# board.net
KiCad netlist of a schematic drawn in EAGLE
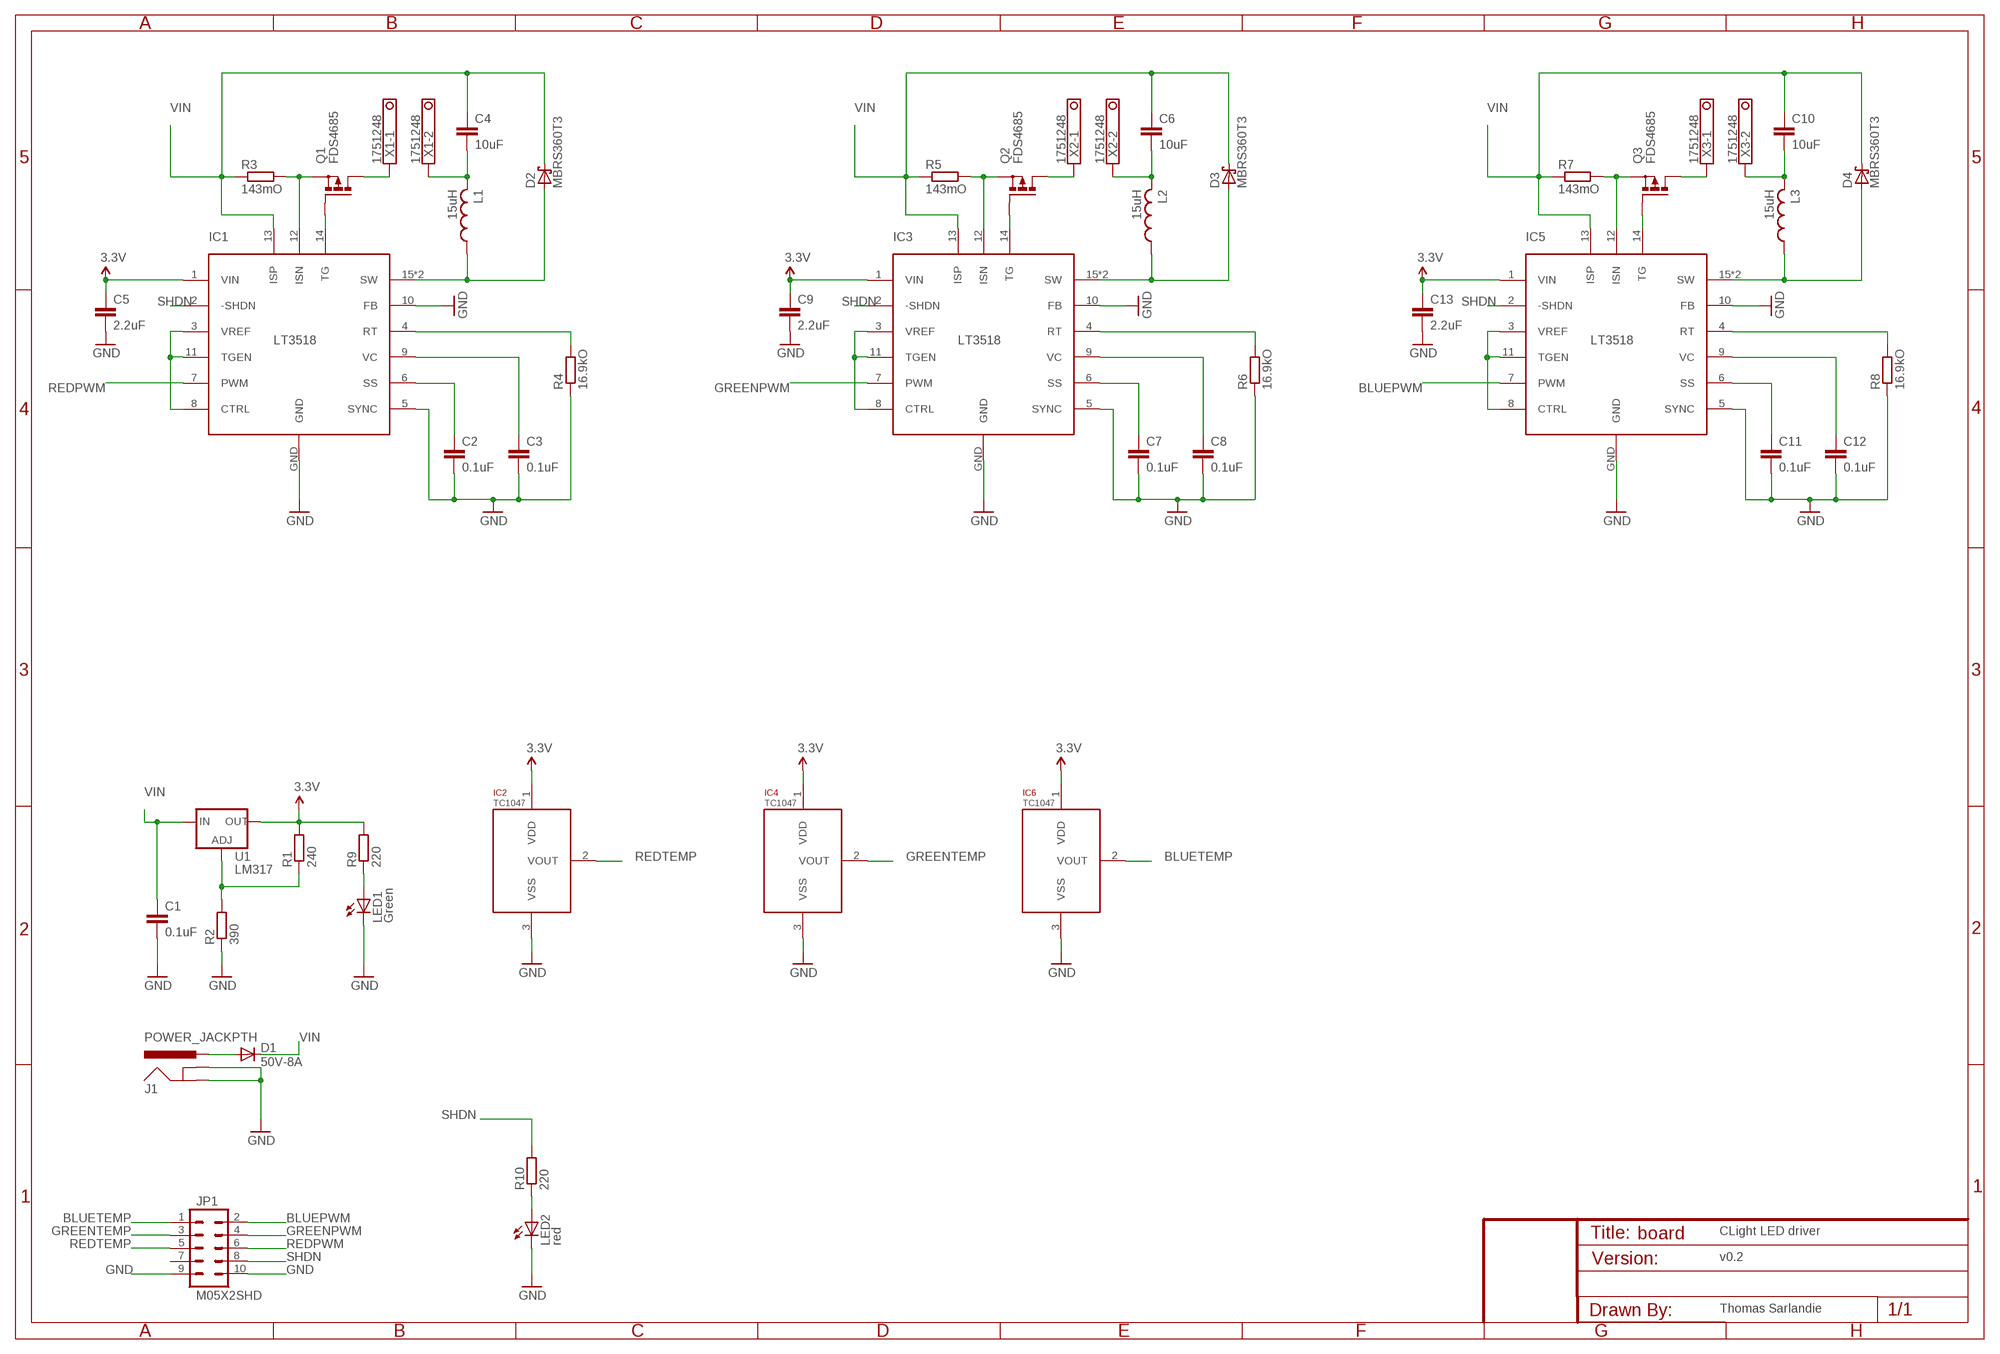
[diagram p0: schematic, sheet 1]

(export (version "E")
  (design (tool "Eeschema 10.0.6"))
  (components
    (comp (ref "C1")
      (value "0.1uF")
      (footprint "eagle-import:C1206")
      (libsource (lib "eagle-import") (part "C-EUC1206"))
    )
    (comp (ref "C2")
      (value "0.1uF")
      (footprint "eagle-import:C1206")
      (libsource (lib "eagle-import") (part "C-EUC1206"))
    )
    (comp (ref "C3")
      (value "0.1uF")
      (footprint "eagle-import:C1206")
      (libsource (lib "eagle-import") (part "C-EUC1206"))
    )
    (comp (ref "C4")
      (value "10uF")
      (footprint "eagle-import:C1206")
      (libsource (lib "eagle-import") (part "C-EUC1206"))
    )
    (comp (ref "C5")
      (value "2.2uF")
      (footprint "eagle-import:C1206")
      (libsource (lib "eagle-import") (part "C-EUC1206"))
    )
    (comp (ref "C6")
      (value "10uF")
      (footprint "eagle-import:C1206")
      (libsource (lib "eagle-import") (part "C-EUC1206"))
    )
    (comp (ref "C7")
      (value "0.1uF")
      (footprint "eagle-import:C1206")
      (libsource (lib "eagle-import") (part "C-EUC1206"))
    )
    (comp (ref "C8")
      (value "0.1uF")
      (footprint "eagle-import:C1206")
      (libsource (lib "eagle-import") (part "C-EUC1206"))
    )
    (comp (ref "C9")
      (value "2.2uF")
      (footprint "eagle-import:C1206")
      (libsource (lib "eagle-import") (part "C-EUC1206"))
    )
    (comp (ref "C10")
      (value "10uF")
      (footprint "eagle-import:C1206")
      (libsource (lib "eagle-import") (part "C-EUC1206"))
    )
    (comp (ref "C11")
      (value "0.1uF")
      (footprint "eagle-import:C1206")
      (libsource (lib "eagle-import") (part "C-EUC1206"))
    )
    (comp (ref "C12")
      (value "0.1uF")
      (footprint "eagle-import:C1206")
      (libsource (lib "eagle-import") (part "C-EUC1206"))
    )
    (comp (ref "C13")
      (value "2.2uF")
      (footprint "eagle-import:C1206")
      (libsource (lib "eagle-import") (part "C-EUC1206"))
    )
    (comp (ref "D1")
      (value "50V-8A")
      (footprint "eagle-import:SMC")
      (libsource (lib "eagle-import") (part "DIODE-SMC"))
    )
    (comp (ref "D2")
      (value "MBRS360T3")
      (footprint "eagle-import:SMC")
      (libsource (lib "eagle-import") (part "MBRS30T34"))
    )
    (comp (ref "D3")
      (value "MBRS360T3")
      (footprint "eagle-import:SMC")
      (libsource (lib "eagle-import") (part "MBRS30T34"))
    )
    (comp (ref "D4")
      (value "MBRS360T3")
      (footprint "eagle-import:SMC")
      (libsource (lib "eagle-import") (part "MBRS30T34"))
    )
    (comp (ref "IC1")
      (value "LT3518TSSOP16-EXPOSED-PAD-LARGE")
      (footprint "eagle-import:TSSOP16-EXPOSED_PAD_LARGE")
      (libsource (lib "eagle-import") (part "LT3518TSSOP16-EXPOSED-PAD-LARGE"))
    )
    (comp (ref "IC2")
      (value "TC1047")
      (footprint "eagle-import:SOT-23B")
      (libsource (lib "eagle-import") (part "TC1047SOT-23B"))
    )
    (comp (ref "IC3")
      (value "LT3518TSSOP16-EXPOSED-PAD-LARGE")
      (footprint "eagle-import:TSSOP16-EXPOSED_PAD_LARGE")
      (libsource (lib "eagle-import") (part "LT3518TSSOP16-EXPOSED-PAD-LARGE"))
    )
    (comp (ref "IC4")
      (value "TC1047")
      (footprint "eagle-import:SOT-23B")
      (libsource (lib "eagle-import") (part "TC1047SOT-23B"))
    )
    (comp (ref "IC5")
      (value "LT3518TSSOP16-EXPOSED-PAD-LARGE")
      (footprint "eagle-import:TSSOP16-EXPOSED_PAD_LARGE")
      (libsource (lib "eagle-import") (part "LT3518TSSOP16-EXPOSED-PAD-LARGE"))
    )
    (comp (ref "IC6")
      (value "TC1047")
      (footprint "eagle-import:SOT-23B")
      (libsource (lib "eagle-import") (part "TC1047SOT-23B"))
    )
    (comp (ref "J1")
      (value "POWER_JACKPTH")
      (footprint "eagle-import:POWER_JACK_PTH")
      (libsource (lib "eagle-import") (part "POWER_JACKPTH"))
    )
    (comp (ref "JP1")
      (value "M05X2SHD")
      (footprint "eagle-import:2X5-SHROUDED")
      (libsource (lib "eagle-import") (part "M05X2SHD"))
    )
    (comp (ref "L1")
      (value "15uH")
      (footprint "eagle-import:L2020")
      (libsource (lib "eagle-import") (part "L-USL2020"))
    )
    (comp (ref "L2")
      (value "15uH")
      (footprint "eagle-import:L2020")
      (libsource (lib "eagle-import") (part "L-USL2020"))
    )
    (comp (ref "L3")
      (value "15uH")
      (footprint "eagle-import:L2020")
      (libsource (lib "eagle-import") (part "L-USL2020"))
    )
    (comp (ref "LED1")
      (value "Green")
      (footprint "eagle-import:LED-1206")
      (libsource (lib "eagle-import") (part "LED1206"))
    )
    (comp (ref "LED2")
      (value "red")
      (footprint "eagle-import:LED-1206")
      (libsource (lib "eagle-import") (part "LED1206"))
    )
    (comp (ref "Q1")
      (value "FDS4685")
      (footprint "eagle-import:SO-08")
      (libsource (lib "eagle-import") (part "P-MOSFET-SO8"))
    )
    (comp (ref "Q2")
      (value "FDS4685")
      (footprint "eagle-import:SO-08")
      (libsource (lib "eagle-import") (part "P-MOSFET-SO8"))
    )
    (comp (ref "Q3")
      (value "FDS4685")
      (footprint "eagle-import:SO-08")
      (libsource (lib "eagle-import") (part "P-MOSFET-SO8"))
    )
    (comp (ref "R1")
      (value "240")
      (footprint "eagle-import:R1206")
      (libsource (lib "eagle-import") (part "R-EU_R1206"))
    )
    (comp (ref "R2")
      (value "390")
      (footprint "eagle-import:R1206")
      (libsource (lib "eagle-import") (part "R-EU_R1206"))
    )
    (comp (ref "R3")
      (value "143mO")
      (footprint "eagle-import:R1206")
      (libsource (lib "eagle-import") (part "R-EU_R1206"))
    )
    (comp (ref "R4")
      (value "16.9kO")
      (footprint "eagle-import:R1206")
      (libsource (lib "eagle-import") (part "R-EU_R1206"))
    )
    (comp (ref "R5")
      (value "143mO")
      (footprint "eagle-import:R1206")
      (libsource (lib "eagle-import") (part "R-EU_R1206"))
    )
    (comp (ref "R6")
      (value "16.9kO")
      (footprint "eagle-import:R1206")
      (libsource (lib "eagle-import") (part "R-EU_R1206"))
    )
    (comp (ref "R7")
      (value "143mO")
      (footprint "eagle-import:R1206")
      (libsource (lib "eagle-import") (part "R-EU_R1206"))
    )
    (comp (ref "R8")
      (value "16.9kO")
      (footprint "eagle-import:R1206")
      (libsource (lib "eagle-import") (part "R-EU_R1206"))
    )
    (comp (ref "R9")
      (value "220")
      (footprint "eagle-import:R1206")
      (libsource (lib "eagle-import") (part "R-EU_R1206"))
    )
    (comp (ref "R10")
      (value "220")
      (footprint "eagle-import:R1206")
      (libsource (lib "eagle-import") (part "R-EU_R1206"))
    )
    (comp (ref "U1")
      (value "LM317")
      (footprint "eagle-import:SOT223")
      (libsource (lib "eagle-import") (part "V_REG_317SMD"))
    )
    (comp (ref "X1")
      (value "1751248")
      (footprint "eagle-import:1751248")
      (libsource (lib "eagle-import") (part "1751248"))
    )
    (comp (ref "X2")
      (value "1751248")
      (footprint "eagle-import:1751248")
      (libsource (lib "eagle-import") (part "1751248"))
    )
    (comp (ref "X3")
      (value "1751248")
      (footprint "eagle-import:1751248")
      (libsource (lib "eagle-import") (part "1751248"))
    )
  )
  (nets
    (net (code "1") (name "/BLUEPWM") (class "Default")
      (node (ref "IC5") (pin "7") (pinfunction "PWM_7") (pintype "bidirectional"))
      (node (ref "JP1") (pin "2") (pinfunction "2_2") (pintype "passive"))
    )
    (net (code "2") (name "/BLUETEMP") (class "Default")
      (node (ref "IC6") (pin "2") (pinfunction "VOUT_2") (pintype "bidirectional"))
      (node (ref "JP1") (pin "1") (pinfunction "1_1") (pintype "passive"))
    )
    (net (code "3") (name "/GREENPWM") (class "Default")
      (node (ref "IC3") (pin "7") (pinfunction "PWM_7") (pintype "bidirectional"))
      (node (ref "JP1") (pin "4") (pinfunction "4_4") (pintype "passive"))
    )
    (net (code "4") (name "/GREENTEMP") (class "Default")
      (node (ref "IC4") (pin "2") (pinfunction "VOUT_2") (pintype "bidirectional"))
      (node (ref "JP1") (pin "3") (pinfunction "3_3") (pintype "passive"))
    )
    (net (code "5") (name "/REDPWM") (class "Default")
      (node (ref "IC1") (pin "7") (pinfunction "PWM_7") (pintype "bidirectional"))
      (node (ref "JP1") (pin "6") (pinfunction "6_6") (pintype "passive"))
    )
    (net (code "6") (name "/REDTEMP") (class "Default")
      (node (ref "IC2") (pin "2") (pinfunction "VOUT_2") (pintype "bidirectional"))
      (node (ref "JP1") (pin "5") (pinfunction "5_5") (pintype "passive"))
    )
    (net (code "7") (name "/SHDN") (class "Default")
      (node (ref "IC1") (pin "2") (pinfunction "-SHDN_2") (pintype "bidirectional"))
      (node (ref "IC3") (pin "2") (pinfunction "-SHDN_2") (pintype "bidirectional"))
      (node (ref "IC5") (pin "2") (pinfunction "-SHDN_2") (pintype "bidirectional"))
      (node (ref "JP1") (pin "8") (pinfunction "8_8") (pintype "passive"))
      (node (ref "R10") (pin "2") (pinfunction "2_2") (pintype "passive"))
    )
    (net (code "8") (name "/VIN") (class "Default")
      (node (ref "C1") (pin "1") (pinfunction "1_1") (pintype "passive"))
      (node (ref "C10") (pin "1") (pinfunction "1_1") (pintype "passive"))
      (node (ref "C4") (pin "1") (pinfunction "1_1") (pintype "passive"))
      (node (ref "C6") (pin "1") (pinfunction "1_1") (pintype "passive"))
      (node (ref "D1") (pin "C") (pinfunction "C_C") (pintype "passive"))
      (node (ref "D2") (pin "C") (pinfunction "C_C") (pintype "passive"))
      (node (ref "D3") (pin "C") (pinfunction "C_C") (pintype "passive"))
      (node (ref "D4") (pin "C") (pinfunction "C_C") (pintype "passive"))
      (node (ref "IC1") (pin "13") (pinfunction "ISP_13") (pintype "bidirectional"))
      (node (ref "IC3") (pin "13") (pinfunction "ISP_13") (pintype "bidirectional"))
      (node (ref "IC5") (pin "13") (pinfunction "ISP_13") (pintype "bidirectional"))
      (node (ref "R3") (pin "1") (pinfunction "1_1") (pintype "passive"))
      (node (ref "R5") (pin "1") (pinfunction "1_1") (pintype "passive"))
      (node (ref "R7") (pin "1") (pinfunction "1_1") (pintype "passive"))
      (node (ref "U1") (pin "3") (pinfunction "IN_3") (pintype "input"))
    )
    (net (code "9") (name "3.3V") (class "Default")
      (node (ref "C13") (pin "1") (pinfunction "1_1") (pintype "passive"))
      (node (ref "C5") (pin "1") (pinfunction "1_1") (pintype "passive"))
      (node (ref "C9") (pin "1") (pinfunction "1_1") (pintype "passive"))
      (node (ref "IC1") (pin "1") (pinfunction "VIN_1") (pintype "bidirectional"))
      (node (ref "IC2") (pin "1") (pinfunction "VDD_1") (pintype "bidirectional"))
      (node (ref "IC3") (pin "1") (pinfunction "VIN_1") (pintype "bidirectional"))
      (node (ref "IC4") (pin "1") (pinfunction "VDD_1") (pintype "bidirectional"))
      (node (ref "IC5") (pin "1") (pinfunction "VIN_1") (pintype "bidirectional"))
      (node (ref "IC6") (pin "1") (pinfunction "VDD_1") (pintype "bidirectional"))
      (node (ref "R1") (pin "2") (pinfunction "2_2") (pintype "passive"))
      (node (ref "R9") (pin "2") (pinfunction "2_2") (pintype "passive"))
      (node (ref "U1") (pin "2") (pinfunction "OUT_2") (pintype "output"))
    )
    (net (code "10") (name "GND") (class "Default")
      (node (ref "C1") (pin "2") (pinfunction "2_2") (pintype "passive"))
      (node (ref "C11") (pin "2") (pinfunction "2_2") (pintype "passive"))
      (node (ref "C12") (pin "2") (pinfunction "2_2") (pintype "passive"))
      (node (ref "C13") (pin "2") (pinfunction "2_2") (pintype "passive"))
      (node (ref "C2") (pin "2") (pinfunction "2_2") (pintype "passive"))
      (node (ref "C3") (pin "2") (pinfunction "2_2") (pintype "passive"))
      (node (ref "C5") (pin "2") (pinfunction "2_2") (pintype "passive"))
      (node (ref "C7") (pin "2") (pinfunction "2_2") (pintype "passive"))
      (node (ref "C8") (pin "2") (pinfunction "2_2") (pintype "passive"))
      (node (ref "C9") (pin "2") (pinfunction "2_2") (pintype "passive"))
      (node (ref "IC1") (pin "10") (pinfunction "FB_10") (pintype "bidirectional"))
      (node (ref "IC1") (pin "5") (pinfunction "SYNC_5") (pintype "bidirectional"))
      (node (ref "IC1") (pin "GND") (pinfunction "GND_GND") (pintype "bidirectional"))
      (node (ref "IC2") (pin "3") (pinfunction "VSS_3") (pintype "bidirectional"))
      (node (ref "IC3") (pin "10") (pinfunction "FB_10") (pintype "bidirectional"))
      (node (ref "IC3") (pin "5") (pinfunction "SYNC_5") (pintype "bidirectional"))
      (node (ref "IC3") (pin "GND") (pinfunction "GND_GND") (pintype "bidirectional"))
      (node (ref "IC4") (pin "3") (pinfunction "VSS_3") (pintype "bidirectional"))
      (node (ref "IC5") (pin "10") (pinfunction "FB_10") (pintype "bidirectional"))
      (node (ref "IC5") (pin "5") (pinfunction "SYNC_5") (pintype "bidirectional"))
      (node (ref "IC5") (pin "GND") (pinfunction "GND_GND") (pintype "bidirectional"))
      (node (ref "IC6") (pin "3") (pinfunction "VSS_3") (pintype "bidirectional"))
      (node (ref "J1") (pin "GND") (pinfunction "GND_GND") (pintype "bidirectional"))
      (node (ref "J1") (pin "GNDBREAK") (pinfunction "GNDBREAK_GNDBREAK") (pintype "bidirectional"))
      (node (ref "JP1") (pin "10") (pinfunction "10_10") (pintype "passive"))
      (node (ref "JP1") (pin "9") (pinfunction "9_9") (pintype "passive"))
      (node (ref "LED1") (pin "C") (pinfunction "C_C") (pintype "passive"))
      (node (ref "LED2") (pin "C") (pinfunction "C_C") (pintype "passive"))
      (node (ref "R2") (pin "1") (pinfunction "1_1") (pintype "passive"))
      (node (ref "R4") (pin "1") (pinfunction "1_1") (pintype "passive"))
      (node (ref "R6") (pin "1") (pinfunction "1_1") (pintype "passive"))
      (node (ref "R8") (pin "1") (pinfunction "1_1") (pintype "passive"))
    )
    (net (code "11") (name "Net-(D1-PadA)") (class "Default")
      (node (ref "D1") (pin "A") (pinfunction "A_A") (pintype "passive"))
      (node (ref "J1") (pin "PWR") (pinfunction "PWR_PWR") (pintype "bidirectional"))
    )
    (net (code "12") (name "Net-(IC1-CTRL)") (class "Default")
      (node (ref "IC1") (pin "11") (pinfunction "TGEN_11") (pintype "bidirectional"))
      (node (ref "IC1") (pin "3") (pinfunction "VREF_3") (pintype "bidirectional"))
      (node (ref "IC1") (pin "8") (pinfunction "CTRL_8") (pintype "bidirectional"))
    )
    (net (code "13") (name "Net-(IC1-ISN)") (class "Default")
      (node (ref "IC1") (pin "12") (pinfunction "ISN_12") (pintype "bidirectional"))
      (node (ref "Q1") (pin "1") (pinfunction "S_1") (pintype "passive"))
      (node (ref "Q1") (pin "2") (pinfunction "S_2") (pintype "passive"))
      (node (ref "Q1") (pin "3") (pinfunction "S_3") (pintype "passive"))
      (node (ref "R3") (pin "2") (pinfunction "2_2") (pintype "passive"))
    )
    (net (code "14") (name "Net-(IC1-RT)") (class "Default")
      (node (ref "IC1") (pin "4") (pinfunction "RT_4") (pintype "bidirectional"))
      (node (ref "R4") (pin "2") (pinfunction "2_2") (pintype "passive"))
    )
    (net (code "15") (name "Net-(IC1-SS)") (class "Default")
      (node (ref "C2") (pin "1") (pinfunction "1_1") (pintype "passive"))
      (node (ref "IC1") (pin "6") (pinfunction "SS_6") (pintype "bidirectional"))
    )
    (net (code "16") (name "Net-(IC1-TG)") (class "Default")
      (node (ref "IC1") (pin "14") (pinfunction "TG_14") (pintype "bidirectional"))
      (node (ref "Q1") (pin "4") (pinfunction "G_4") (pintype "passive"))
    )
    (net (code "17") (name "Net-(IC1-VC)") (class "Default")
      (node (ref "C3") (pin "1") (pinfunction "1_1") (pintype "passive"))
      (node (ref "IC1") (pin "9") (pinfunction "VC_9") (pintype "bidirectional"))
    )
    (net (code "18") (name "Net-(IC3-CTRL)") (class "Default")
      (node (ref "IC3") (pin "11") (pinfunction "TGEN_11") (pintype "bidirectional"))
      (node (ref "IC3") (pin "3") (pinfunction "VREF_3") (pintype "bidirectional"))
      (node (ref "IC3") (pin "8") (pinfunction "CTRL_8") (pintype "bidirectional"))
    )
    (net (code "19") (name "Net-(IC3-ISN)") (class "Default")
      (node (ref "IC3") (pin "12") (pinfunction "ISN_12") (pintype "bidirectional"))
      (node (ref "Q2") (pin "1") (pinfunction "S_1") (pintype "passive"))
      (node (ref "Q2") (pin "2") (pinfunction "S_2") (pintype "passive"))
      (node (ref "Q2") (pin "3") (pinfunction "S_3") (pintype "passive"))
      (node (ref "R5") (pin "2") (pinfunction "2_2") (pintype "passive"))
    )
    (net (code "20") (name "Net-(IC3-RT)") (class "Default")
      (node (ref "IC3") (pin "4") (pinfunction "RT_4") (pintype "bidirectional"))
      (node (ref "R6") (pin "2") (pinfunction "2_2") (pintype "passive"))
    )
    (net (code "21") (name "Net-(IC3-SS)") (class "Default")
      (node (ref "C7") (pin "1") (pinfunction "1_1") (pintype "passive"))
      (node (ref "IC3") (pin "6") (pinfunction "SS_6") (pintype "bidirectional"))
    )
    (net (code "22") (name "Net-(IC3-TG)") (class "Default")
      (node (ref "IC3") (pin "14") (pinfunction "TG_14") (pintype "bidirectional"))
      (node (ref "Q2") (pin "4") (pinfunction "G_4") (pintype "passive"))
    )
    (net (code "23") (name "Net-(IC3-VC)") (class "Default")
      (node (ref "C8") (pin "1") (pinfunction "1_1") (pintype "passive"))
      (node (ref "IC3") (pin "9") (pinfunction "VC_9") (pintype "bidirectional"))
    )
    (net (code "24") (name "Net-(IC5-CTRL)") (class "Default")
      (node (ref "IC5") (pin "11") (pinfunction "TGEN_11") (pintype "bidirectional"))
      (node (ref "IC5") (pin "3") (pinfunction "VREF_3") (pintype "bidirectional"))
      (node (ref "IC5") (pin "8") (pinfunction "CTRL_8") (pintype "bidirectional"))
    )
    (net (code "25") (name "Net-(IC5-ISN)") (class "Default")
      (node (ref "IC5") (pin "12") (pinfunction "ISN_12") (pintype "bidirectional"))
      (node (ref "Q3") (pin "1") (pinfunction "S_1") (pintype "passive"))
      (node (ref "Q3") (pin "2") (pinfunction "S_2") (pintype "passive"))
      (node (ref "Q3") (pin "3") (pinfunction "S_3") (pintype "passive"))
      (node (ref "R7") (pin "2") (pinfunction "2_2") (pintype "passive"))
    )
    (net (code "26") (name "Net-(IC5-RT)") (class "Default")
      (node (ref "IC5") (pin "4") (pinfunction "RT_4") (pintype "bidirectional"))
      (node (ref "R8") (pin "2") (pinfunction "2_2") (pintype "passive"))
    )
    (net (code "27") (name "Net-(IC5-SS)") (class "Default")
      (node (ref "C11") (pin "1") (pinfunction "1_1") (pintype "passive"))
      (node (ref "IC5") (pin "6") (pinfunction "SS_6") (pintype "bidirectional"))
    )
    (net (code "28") (name "Net-(IC5-TG)") (class "Default")
      (node (ref "IC5") (pin "14") (pinfunction "TG_14") (pintype "bidirectional"))
      (node (ref "Q3") (pin "4") (pinfunction "G_4") (pintype "passive"))
    )
    (net (code "29") (name "Net-(IC5-VC)") (class "Default")
      (node (ref "C12") (pin "1") (pinfunction "1_1") (pintype "passive"))
      (node (ref "IC5") (pin "9") (pinfunction "VC_9") (pintype "bidirectional"))
    )
    (net (code "30") (name "Net-(L1-1)") (class "Default")
      (node (ref "D2") (pin "A") (pinfunction "A_A") (pintype "passive"))
      (node (ref "IC1") (pin "15") (pinfunction "SW_15") (pintype "bidirectional"))
      (node (ref "IC1") (pin "16") (pinfunction "SW_16") (pintype "bidirectional"))
      (node (ref "L1") (pin "P$1") (pinfunction "1_P$1") (pintype "passive"))
    )
    (net (code "31") (name "Net-(L1-2)") (class "Default")
      (node (ref "C4") (pin "2") (pinfunction "2_2") (pintype "passive"))
      (node (ref "L1") (pin "P$2") (pinfunction "2_P$2") (pintype "passive"))
      (node (ref "X1") (pin "2") (pinfunction "K_2") (pintype "passive"))
    )
    (net (code "32") (name "Net-(L2-1)") (class "Default")
      (node (ref "D3") (pin "A") (pinfunction "A_A") (pintype "passive"))
      (node (ref "IC3") (pin "15") (pinfunction "SW_15") (pintype "bidirectional"))
      (node (ref "IC3") (pin "16") (pinfunction "SW_16") (pintype "bidirectional"))
      (node (ref "L2") (pin "P$1") (pinfunction "1_P$1") (pintype "passive"))
    )
    (net (code "33") (name "Net-(L2-2)") (class "Default")
      (node (ref "C6") (pin "2") (pinfunction "2_2") (pintype "passive"))
      (node (ref "L2") (pin "P$2") (pinfunction "2_P$2") (pintype "passive"))
      (node (ref "X2") (pin "2") (pinfunction "K_2") (pintype "passive"))
    )
    (net (code "34") (name "Net-(L3-1)") (class "Default")
      (node (ref "D4") (pin "A") (pinfunction "A_A") (pintype "passive"))
      (node (ref "IC5") (pin "15") (pinfunction "SW_15") (pintype "bidirectional"))
      (node (ref "IC5") (pin "16") (pinfunction "SW_16") (pintype "bidirectional"))
      (node (ref "L3") (pin "P$1") (pinfunction "1_P$1") (pintype "passive"))
    )
    (net (code "35") (name "Net-(L3-2)") (class "Default")
      (node (ref "C10") (pin "2") (pinfunction "2_2") (pintype "passive"))
      (node (ref "L3") (pin "P$2") (pinfunction "2_P$2") (pintype "passive"))
      (node (ref "X3") (pin "2") (pinfunction "K_2") (pintype "passive"))
    )
    (net (code "36") (name "Net-(LED1-PadA)") (class "Default")
      (node (ref "LED1") (pin "A") (pinfunction "A_A") (pintype "passive"))
      (node (ref "R9") (pin "1") (pinfunction "1_1") (pintype "passive"))
    )
    (net (code "37") (name "Net-(LED2-PadA)") (class "Default")
      (node (ref "LED2") (pin "A") (pinfunction "A_A") (pintype "passive"))
      (node (ref "R10") (pin "1") (pinfunction "1_1") (pintype "passive"))
    )
    (net (code "38") (name "Net-(U1-ADJ)") (class "Default")
      (node (ref "R1") (pin "1") (pinfunction "1_1") (pintype "passive"))
      (node (ref "R2") (pin "2") (pinfunction "2_2") (pintype "passive"))
      (node (ref "U1") (pin "1") (pinfunction "ADJ_1") (pintype "input"))
    )
    (net (code "39") (name "Net-(X1A-K)") (class "Default")
      (node (ref "Q1") (pin "5") (pinfunction "D_5") (pintype "passive"))
      (node (ref "Q1") (pin "6") (pinfunction "D_6") (pintype "passive"))
      (node (ref "Q1") (pin "7") (pinfunction "D_7") (pintype "passive"))
      (node (ref "Q1") (pin "8") (pinfunction "D_8") (pintype "passive"))
      (node (ref "X1") (pin "1") (pinfunction "K_1") (pintype "passive"))
    )
    (net (code "40") (name "Net-(X2A-K)") (class "Default")
      (node (ref "Q2") (pin "5") (pinfunction "D_5") (pintype "passive"))
      (node (ref "Q2") (pin "6") (pinfunction "D_6") (pintype "passive"))
      (node (ref "Q2") (pin "7") (pinfunction "D_7") (pintype "passive"))
      (node (ref "Q2") (pin "8") (pinfunction "D_8") (pintype "passive"))
      (node (ref "X2") (pin "1") (pinfunction "K_1") (pintype "passive"))
    )
    (net (code "41") (name "Net-(X3A-K)") (class "Default")
      (node (ref "Q3") (pin "5") (pinfunction "D_5") (pintype "passive"))
      (node (ref "Q3") (pin "6") (pinfunction "D_6") (pintype "passive"))
      (node (ref "Q3") (pin "7") (pinfunction "D_7") (pintype "passive"))
      (node (ref "Q3") (pin "8") (pinfunction "D_8") (pintype "passive"))
      (node (ref "X3") (pin "1") (pinfunction "K_1") (pintype "passive"))
    )
    (net (code "42") (name "unconnected-(JP1-Pad7)") (class "Default")
      (node (ref "JP1") (pin "7") (pinfunction "7_7") (pintype "passive"))
    )
  )
)
